# percepcao_externa_alimentacao.net
KiCad netlist of a schematic drawn in Altium Designer
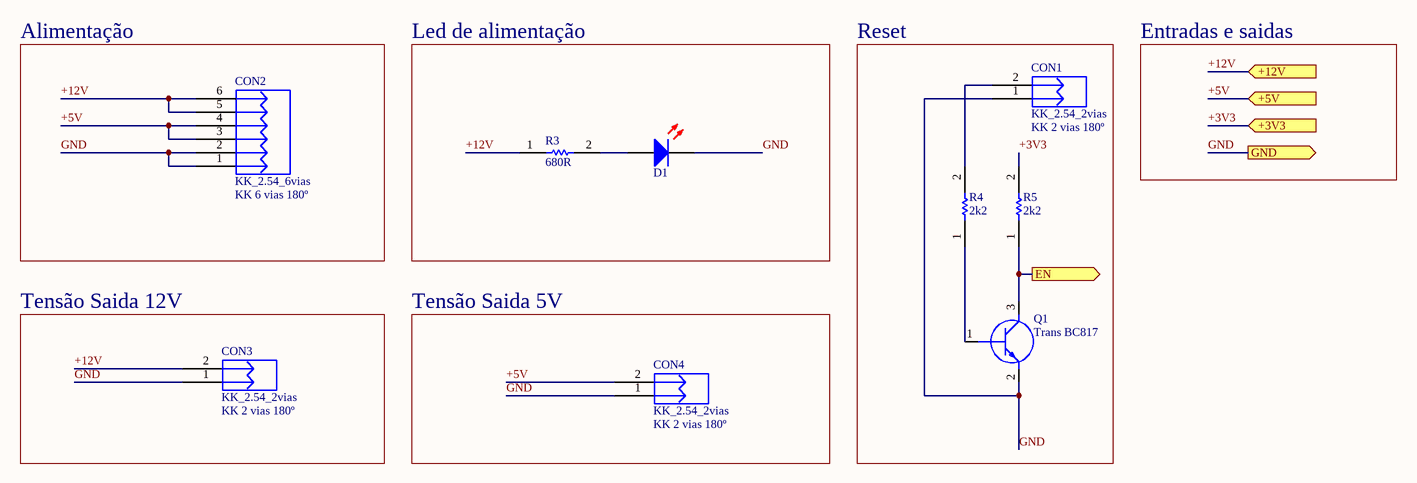
[diagram p0: percepcao_externa_alimentacao.SchDoc]

(export (version "E")
  (design (tool "Eeschema 10.0.6"))
  (components
    (comp (ref "CON1")
      (value "KK_2.54_2vias")
      (footprint "KK_2VIAS_180º")
      (description "Conector KK 2.54mm 2 vias")
      (fields (field (name "VALOR") "KK 2 vias 180º"))
      (libsource (lib "Sinaliza玢o_Official") (part "KK_2.54_2vias"))
    )
    (comp (ref "CON2")
      (value "KK_2.54_6vias")
      (footprint "KK_6vias_180°")
      (description "Conector KK 2.54mm 6 vias")
      (fields (field (name "VALOR") "KK 6 vias 180º"))
      (libsource (lib "Sinaliza玢o_Official") (part "KK_2.54_6vias"))
    )
    (comp (ref "CON3")
      (value "KK_2.54_2vias")
      (footprint "KK_2VIAS_180º")
      (description "Conector KK 2.54mm 2 vias")
      (fields (field (name "VALOR") "KK 2 vias 180º"))
      (libsource (lib "Sinaliza玢o_Official") (part "KK_2.54_2vias"))
    )
    (comp (ref "CON4")
      (value "KK_2.54_2vias")
      (footprint "KK_2VIAS_180º")
      (description "Conector KK 2.54mm 2 vias")
      (fields (field (name "VALOR") "KK 2 vias 180º"))
      (libsource (lib "Sinaliza玢o_Official") (part "KK_2.54_2vias"))
    )
    (comp (ref "D1")
      (value "LED 3MM RED")
      (footprint "LED RED")
      (fields (field (name "MANUFACTURER") "Paralight") (field (name "MANUFACTURER PART NUMBER") "IMP585"))
      (libsource (lib "Sinaliza玢o_Official") (part "LED 3MM RED"))
    )
    (comp (ref "Q1")
      (value "Trans BC817")
      (footprint "SOT96P240X110-3N")
      (description "Transistor BJT NPN BC817-25-7-F")
      (fields
        (field (name "MANUFACTURER_PART_NUMBER") "BC817-25-7-F")
        (field (name "MOUSER PART NUMBER") "621-BC817-25-7-F")
      )
      (libsource (lib "Sinaliza玢o_Official") (part "Trans BC817"))
    )
    (comp (ref "R3")
      (value "680R")
      (footprint "RESC3216X60N")
      (description "Resistor")
      (fields
        (field (name "MANUFACTURER_PART_NUMBER") "CRCW12064K70FKEA")
        (field (name "MOUSER PART NUMBER") "71-CRCW1206-4.7K-E3")
      )
      (libsource (lib "Sinaliza玢o_Official") (part "Resistor 1206"))
    )
    (comp (ref "R4")
      (value "2k2")
      (footprint "RESC3216X60N")
      (description "Resistor")
      (fields
        (field (name "MANUFACTURER_PART_NUMBER") "CRCW12064K70FKEA")
        (field (name "MOUSER PART NUMBER") "71-CRCW1206-4.7K-E3")
      )
      (libsource (lib "Sinaliza玢o_Official") (part "Resistor 1206"))
    )
    (comp (ref "R5")
      (value "2k2")
      (footprint "RESC3216X60N")
      (description "Resistor")
      (fields
        (field (name "MANUFACTURER_PART_NUMBER") "CRCW12064K70FKEA")
        (field (name "MOUSER PART NUMBER") "71-CRCW1206-4.7K-E3")
      )
      (libsource (lib "Sinaliza玢o_Official") (part "Resistor 1206"))
    )
  )
  (nets
    (net (code "1") (name "/+3V3") (class "Default")
      (node (ref "R5") (pin "2") (pinfunction "2_2") (pintype "passive"))
    )
    (net (code "2") (name "/+5V") (class "Default")
      (node (ref "CON2") (pin "3") (pintype "passive"))
      (node (ref "CON2") (pin "4") (pintype "passive"))
      (node (ref "CON4") (pin "2") (pintype "passive"))
    )
    (net (code "3") (name "/+12V") (class "Default")
      (node (ref "CON2") (pin "5") (pintype "passive"))
      (node (ref "CON2") (pin "6") (pintype "passive"))
      (node (ref "CON3") (pin "2") (pintype "passive"))
      (node (ref "R3") (pin "1") (pinfunction "1_1") (pintype "passive"))
    )
    (net (code "4") (name "/EN") (class "Default")
      (node (ref "Q1") (pin "3") (pinfunction "C_3") (pintype "passive"))
      (node (ref "R5") (pin "1") (pinfunction "1_1") (pintype "passive"))
    )
    (net (code "5") (name "/GND") (class "Default")
      (node (ref "CON1") (pin "1") (pintype "passive"))
      (node (ref "CON2") (pin "1") (pintype "passive"))
      (node (ref "CON2") (pin "2") (pintype "passive"))
      (node (ref "CON3") (pin "1") (pintype "passive"))
      (node (ref "CON4") (pin "1") (pintype "passive"))
      (node (ref "D1") (pin "2") (pinfunction "K_2") (pintype "passive"))
      (node (ref "Q1") (pin "2") (pinfunction "E_2") (pintype "passive"))
    )
    (net (code "6") (name "Net-(CON1-Pad2)") (class "Default")
      (node (ref "CON1") (pin "2") (pintype "passive"))
      (node (ref "R4") (pin "2") (pinfunction "2_2") (pintype "passive"))
    )
    (net (code "7") (name "Net-(D1-A)") (class "Default")
      (node (ref "D1") (pin "1") (pinfunction "A_1") (pintype "passive"))
      (node (ref "R3") (pin "2") (pinfunction "2_2") (pintype "passive"))
    )
    (net (code "8") (name "Net-(Q1-B)") (class "Default")
      (node (ref "Q1") (pin "1") (pinfunction "B_1") (pintype "passive"))
      (node (ref "R4") (pin "1") (pinfunction "1_1") (pintype "passive"))
    )
  )
)
